# BTL_mach_nap_acquy_12v_chia_khoi.net
KiCad netlist of a schematic drawn in Altium Designer
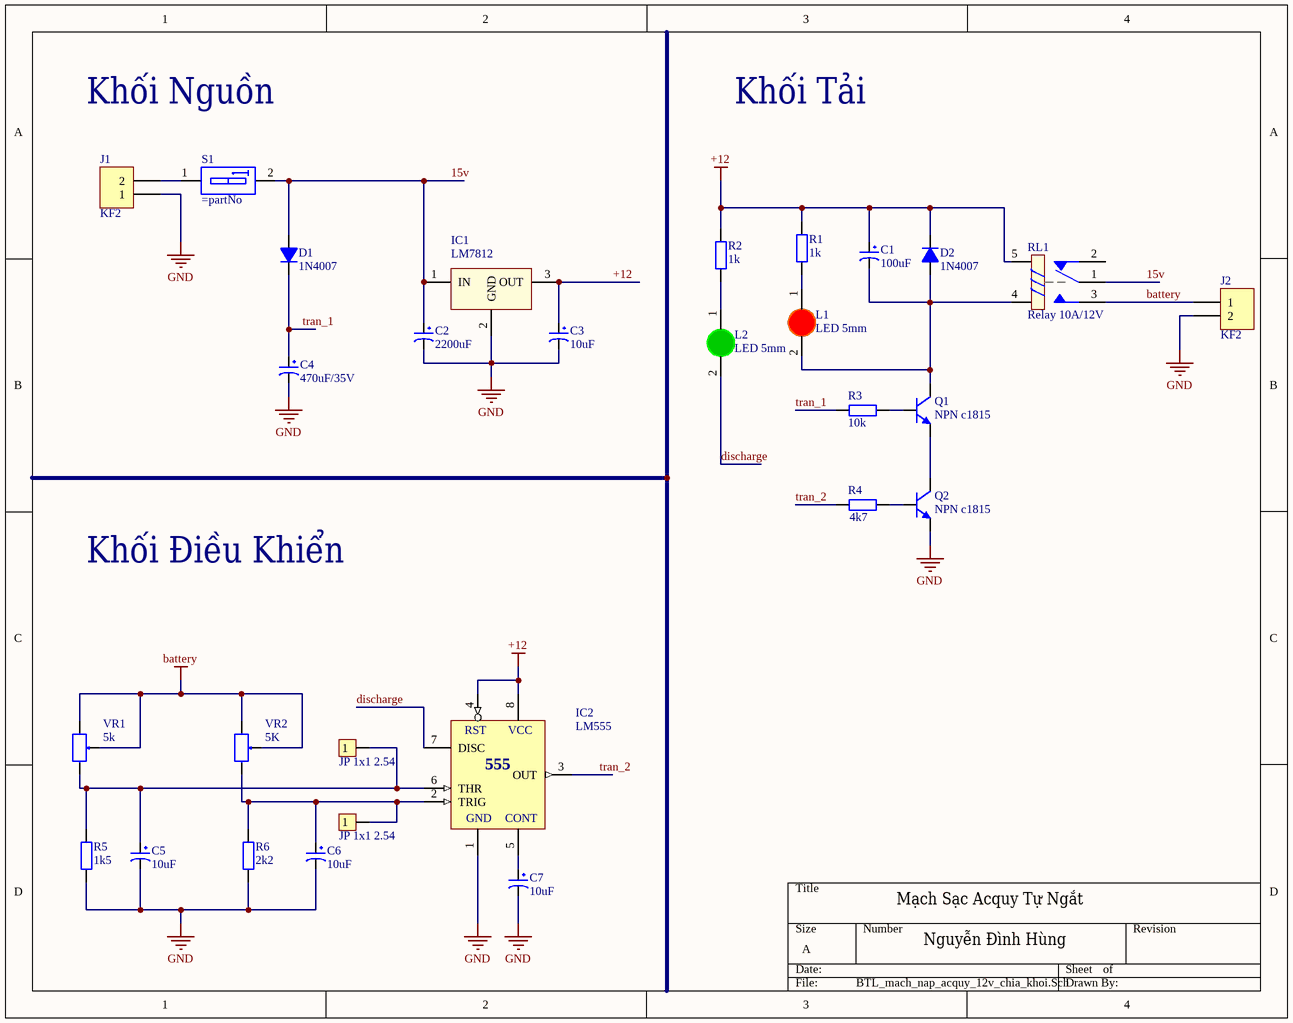
[diagram p0: BTL_mach_nap_acquy_12v_chia_khoi.SchDoc]

(export (version "E")
  (design (tool "Eeschema 10.0.6"))
  (components
    (comp (ref "C1")
      (value "100uF")
      (footprint "tu hoa 5mm")
      (description "Cắm")
      (libsource (lib "Altium_Lib_by_KhueNguyenCreator") (part "Tu Hoa 100uF 25V 6x11"))
    )
    (comp (ref "C2")
      (value "2200uF")
      (footprint "tu hoa 13mm")
      (description "Cắm")
      (libsource (lib "Altium_Lib_by_KhueNguyenCreator") (part "Tu Hoa 2200uF 25V 13x20"))
    )
    (comp (ref "C3")
      (value "10uF")
      (footprint "CP1/2")
      (description "Cap P  0,1uF < 22uF , 16 - 50V")
      (libsource (lib "Altium_Devzone") (part "CP1"))
    )
    (comp (ref "C4")
      (value "470uF/35V")
      (footprint "CP1.5/3.4")
      (description "Cap 100uF/35V - 470uF/16V")
      (libsource (lib "Altium_Devzone") (part "CP3"))
    )
    (comp (ref "C5")
      (value "10uF")
      (footprint "CP1/2")
      (description "Cap P  0,1uF < 22uF , 16 - 50V")
      (libsource (lib "Altium_Devzone") (part "CP1"))
    )
    (comp (ref "C6")
      (value "10uF")
      (footprint "CP1/2")
      (description "Cap P  0,1uF < 22uF , 16 - 50V")
      (libsource (lib "Altium_Devzone") (part "CP1"))
    )
    (comp (ref "C7")
      (value "10uF")
      (footprint "CP1/2")
      (description "Cap P  0,1uF < 22uF , 16 - 50V")
      (libsource (lib "Altium_Devzone") (part "CP1"))
    )
    (comp (ref "D1")
      (value "1N4007")
      (footprint "D1A")
      (description "Diode 1A")
      (libsource (lib "Altium_Devzone") (part "Diode 1A"))
    )
    (comp (ref "D2")
      (value "1N4007")
      (footprint "D1A")
      (description "Diode 1A")
      (libsource (lib "Altium_Devzone") (part "Diode 1A"))
    )
    (comp (ref "IC1")
      (value "LM7812")
      (footprint "QTO-220H3")
      (description "On ap +, from + 5 to + 24VDC")
      (libsource (lib "Altium_Devzone") (part "LM78xx"))
    )
    (comp (ref "IC2")
      (value "LM555")
      (footprint "DIP8")
      (description "Timer Circuits")
      (libsource (lib "Altium_Devzone") (part "LM555"))
    )
    (comp (ref "J1")
      (value "KF2")
      (footprint "KF2-3.5")
      (fields
        (field (name "MANUFACTURER") "Würth Elektronik eiSos GmbH")
        (field (name "PARTNO") "691103110002")
        (field (name "CREATED BY") "Karrer Zheng")
      )
      (libsource (lib "Altium Library") (part "KF2"))
    )
    (comp (ref "J2")
      (value "KF2")
      (footprint "KF2-3.5")
      (fields
        (field (name "MANUFACTURER") "Würth Elektronik eiSos GmbH")
        (field (name "PARTNO") "691103110002")
        (field (name "CREATED BY") "Karrer Zheng")
      )
      (libsource (lib "") (part "KF2_1"))
    )
    (comp (ref "JP1")
      (value "JP 1x1 2.54")
      (footprint "JP 1x1 DT")
      (description "Cắm")
      (libsource (lib "Altium_Lib_by_KhueNguyenCreator") (part "JP 1x1 2.54 Duc Cong"))
    )
    (comp (ref "JP2")
      (value "JP 1x1 2.54")
      (footprint "JP 1x1 DT")
      (description "Cắm")
      (libsource (lib "Altium_Lib_by_KhueNguyenCreator") (part "JP 1x1 2.54 Duc Cong"))
    )
    (comp (ref "L1")
      (value "LED 5mm")
      (footprint "LED-5MM-RED")
      (description "Cắm")
      (libsource (lib "Altium_Lib_by_KhueNguyenCreator") (part "LED 5mm Do"))
    )
    (comp (ref "L2")
      (value "LED 5mm")
      (footprint "LED-5MM-Green")
      (description "Cắm")
      (libsource (lib "Altium_Lib_by_KhueNguyenCreator") (part "LED 5mm Xanh La"))
    )
    (comp (ref "Q1")
      (value "NPN c1815")
      (footprint "TRAN-LOWPOWER")
      (description "NPN General")
      (fields (field (name "PUBLISHER") "Altium Limited"))
      (libsource (lib "Altium_Devzone") (part "NPN"))
    )
    (comp (ref "Q2")
      (value "NPN c1815")
      (footprint "TRAN-LOWPOWER")
      (description "NPN General")
      (fields (field (name "PUBLISHER") "Altium Limited"))
      (libsource (lib "Altium_Devzone") (part "NPN"))
    )
    (comp (ref "R1")
      (value "1k")
      (footprint "R1/4W")
      (description "Resistor 1/4W")
      (libsource (lib "Altium_Devzone") (part "R1/4W"))
    )
    (comp (ref "R2")
      (value "1k")
      (footprint "R1/4W")
      (description "Resistor 1/4W")
      (libsource (lib "Altium_Devzone") (part "R1/4W"))
    )
    (comp (ref "R3")
      (value "10k")
      (footprint "R1/4W")
      (description "Resistor 1/4W")
      (libsource (lib "Altium_Devzone") (part "R1/4W"))
    )
    (comp (ref "R4")
      (value "4k7")
      (footprint "R1/4W")
      (description "Resistor 1/4W")
      (libsource (lib "Altium_Devzone") (part "R1/4W"))
    )
    (comp (ref "R5")
      (value "1k5")
      (footprint "R1/4W")
      (description "Resistor 1/4W")
      (libsource (lib "Altium_Devzone") (part "R1/4W"))
    )
    (comp (ref "R6")
      (value "2k2")
      (footprint "R1/4W")
      (description "Resistor 1/4W")
      (libsource (lib "Altium_Devzone") (part "R1/4W"))
    )
    (comp (ref "RL1")
      (value "Relay 10A/12V")
      (footprint "RELAY 5")
      (description "Relay SPDT,10A - 12VDC 5 Pin")
      (libsource (lib "Altium_Devzone") (part "Relay 5"))
    )
    (comp (ref "S1")
      (value "~")
      (footprint "SW-DIP1")
      (description "WS-DITV 2.54 mm small compact THT flat actuator with top tape")
      (fields
        (field (name "MANUFACTURER") "Wurth Elektronik")
        (field (name "PART NO.") "418127160901")
        (field (name "CREATED BY") "Baojun Chen")
      )
      (libsource (lib "Altium Library") (part "SWDIP1"))
    )
    (comp (ref "VR1")
      (value "5k")
      (footprint "VR1")
      (description "Var Resistor")
      (libsource (lib "Altium_Devzone") (part "VR"))
    )
    (comp (ref "VR2")
      (value "5K")
      (footprint "VR1")
      (description "Var Resistor")
      (libsource (lib "Altium_Devzone") (part "VR"))
    )
  )
  (nets
    (net (code "1") (name "+12") (class "Default")
      (node (ref "C1") (pin "1") (pinfunction "1_1") (pintype "passive"))
      (node (ref "C3") (pin "1") (pinfunction "1_1") (pintype "passive"))
      (node (ref "D2") (pin "2") (pinfunction "K_2") (pintype "passive"))
      (node (ref "IC1") (pin "3") (pinfunction "OUT_3") (pintype "passive"))
      (node (ref "IC2") (pin "4") (pinfunction "RST_4") (pintype "input"))
      (node (ref "IC2") (pin "8") (pinfunction "VCC_8") (pintype "power_in"))
      (node (ref "R1") (pin "2") (pinfunction "2_2") (pintype "passive"))
      (node (ref "R2") (pin "2") (pinfunction "2_2") (pintype "passive"))
      (node (ref "RL1") (pin "5") (pinfunction "5_5") (pintype "passive"))
    )
    (net (code "2") (name "/15v") (class "Default")
      (node (ref "C2") (pin "1") (pinfunction "1_1") (pintype "passive"))
      (node (ref "D1") (pin "1") (pinfunction "A_1") (pintype "passive"))
      (node (ref "IC1") (pin "1") (pinfunction "IN_1") (pintype "passive"))
      (node (ref "RL1") (pin "1") (pinfunction "1_1") (pintype "passive"))
      (node (ref "S1") (pin "2") (pinfunction "2_2") (pintype "passive"))
    )
    (net (code "3") (name "/discharge") (class "Default")
      (node (ref "IC2") (pin "7") (pinfunction "DISC_7") (pintype "open_collector"))
      (node (ref "L2") (pin "2") (pinfunction "K_2") (pintype "passive"))
    )
    (net (code "4") (name "/tran_1") (class "Default")
      (node (ref "C4") (pin "1") (pinfunction "1_1") (pintype "passive"))
      (node (ref "D1") (pin "2") (pinfunction "K_2") (pintype "passive"))
      (node (ref "R3") (pin "2") (pinfunction "2_2") (pintype "passive"))
    )
    (net (code "5") (name "/tran_2") (class "Default")
      (node (ref "IC2") (pin "3") (pinfunction "OUT_3") (pintype "output"))
      (node (ref "R4") (pin "2") (pinfunction "2_2") (pintype "passive"))
    )
    (net (code "6") (name "GND") (class "Default")
      (node (ref "C2") (pin "2") (pinfunction "2_2") (pintype "passive"))
      (node (ref "C3") (pin "2") (pinfunction "2_2") (pintype "passive"))
      (node (ref "C4") (pin "2") (pinfunction "2_2") (pintype "passive"))
      (node (ref "C5") (pin "2") (pinfunction "2_2") (pintype "passive"))
      (node (ref "C6") (pin "2") (pinfunction "2_2") (pintype "passive"))
      (node (ref "C7") (pin "2") (pinfunction "2_2") (pintype "passive"))
      (node (ref "IC1") (pin "2") (pinfunction "GND_2") (pintype "passive"))
      (node (ref "IC2") (pin "1") (pinfunction "GND_1") (pintype "power_in"))
      (node (ref "J1") (pin "1") (pinfunction "1_1") (pintype "passive"))
      (node (ref "J2") (pin "2") (pinfunction "2_2") (pintype "passive"))
      (node (ref "Q2") (pin "1") (pinfunction "E_1") (pintype "passive"))
      (node (ref "R5") (pin "1") (pinfunction "1_1") (pintype "passive"))
      (node (ref "R6") (pin "1") (pinfunction "1_1") (pintype "passive"))
    )
    (net (code "7") (name "Net-(D2-A)") (class "Default")
      (node (ref "C1") (pin "2") (pinfunction "2_2") (pintype "passive"))
      (node (ref "D2") (pin "1") (pinfunction "A_1") (pintype "passive"))
      (node (ref "L1") (pin "2") (pinfunction "K_2") (pintype "passive"))
      (node (ref "Q1") (pin "2") (pinfunction "C_2") (pintype "passive"))
      (node (ref "RL1") (pin "4") (pinfunction "4_4") (pintype "passive"))
    )
    (net (code "8") (name "Net-(IC2-CONT)") (class "Default")
      (node (ref "C7") (pin "1") (pinfunction "1_1") (pintype "passive"))
      (node (ref "IC2") (pin "5") (pinfunction "CONT_5") (pintype "passive"))
    )
    (net (code "9") (name "Net-(IC2-THR)") (class "Default")
      (node (ref "C5") (pin "1") (pinfunction "1_1") (pintype "passive"))
      (node (ref "IC2") (pin "6") (pinfunction "THR_6") (pintype "input"))
      (node (ref "JP1") (pin "1") (pinfunction "1_1") (pintype "passive"))
      (node (ref "R5") (pin "2") (pinfunction "2_2") (pintype "passive"))
      (node (ref "VR1") (pin "3") (pinfunction "3_3") (pintype "passive"))
    )
    (net (code "10") (name "Net-(IC2-TRIG)") (class "Default")
      (node (ref "C6") (pin "1") (pinfunction "1_1") (pintype "passive"))
      (node (ref "IC2") (pin "2") (pinfunction "TRIG_2") (pintype "input"))
      (node (ref "JP2") (pin "1") (pinfunction "1_1") (pintype "passive"))
      (node (ref "R6") (pin "2") (pinfunction "2_2") (pintype "passive"))
      (node (ref "VR2") (pin "3") (pinfunction "3_3") (pintype "passive"))
    )
    (net (code "11") (name "Net-(J1-Pad2)") (class "Default")
      (node (ref "J1") (pin "2") (pinfunction "2_2") (pintype "passive"))
      (node (ref "S1") (pin "1") (pinfunction "1_1") (pintype "passive"))
    )
    (net (code "12") (name "Net-(L1-A)") (class "Default")
      (node (ref "L1") (pin "1") (pinfunction "A_1") (pintype "passive"))
      (node (ref "R1") (pin "1") (pinfunction "1_1") (pintype "passive"))
    )
    (net (code "13") (name "Net-(L2-A)") (class "Default")
      (node (ref "L2") (pin "1") (pinfunction "A_1") (pintype "passive"))
      (node (ref "R2") (pin "1") (pinfunction "1_1") (pintype "passive"))
    )
    (net (code "14") (name "Net-(Q1-B)") (class "Default")
      (node (ref "Q1") (pin "3") (pinfunction "B_3") (pintype "passive"))
      (node (ref "R3") (pin "1") (pinfunction "1_1") (pintype "passive"))
    )
    (net (code "15") (name "Net-(Q1-E)") (class "Default")
      (node (ref "Q1") (pin "1") (pinfunction "E_1") (pintype "passive"))
      (node (ref "Q2") (pin "2") (pinfunction "C_2") (pintype "passive"))
    )
    (net (code "16") (name "Net-(Q2-B)") (class "Default")
      (node (ref "Q2") (pin "3") (pinfunction "B_3") (pintype "passive"))
      (node (ref "R4") (pin "1") (pinfunction "1_1") (pintype "passive"))
    )
    (net (code "17") (name "battery") (class "Default")
      (node (ref "J2") (pin "1") (pinfunction "1_1") (pintype "passive"))
      (node (ref "RL1") (pin "3") (pinfunction "3_3") (pintype "passive"))
      (node (ref "VR1") (pin "1") (pinfunction "1_1") (pintype "passive"))
      (node (ref "VR1") (pin "2") (pinfunction "2_2") (pintype "passive"))
      (node (ref "VR2") (pin "1") (pinfunction "1_1") (pintype "passive"))
      (node (ref "VR2") (pin "2") (pinfunction "2_2") (pintype "passive"))
    )
    (net (code "18") (name "unconnected-(RL1-Pad2)") (class "Default")
      (node (ref "RL1") (pin "2") (pinfunction "2_2") (pintype "passive"))
    )
  )
)
